# design.net
KiCad netlist of a schematic drawn in Altium Designer
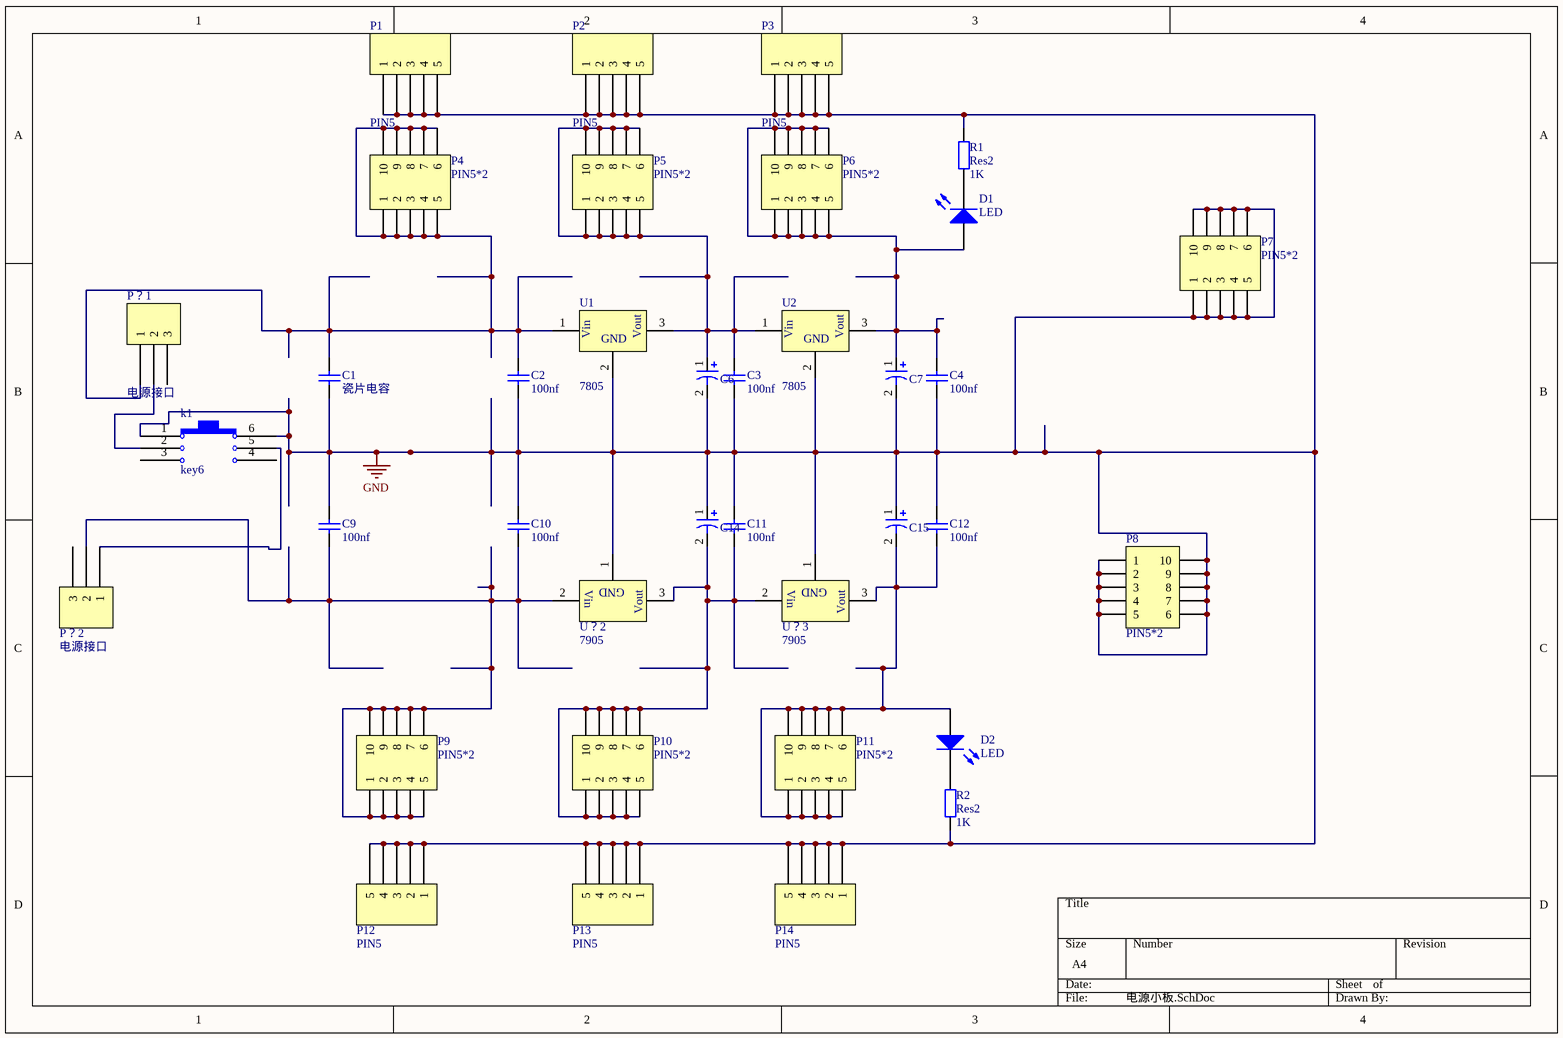
[diagram p0: 电源小板.SchDoc]

(export (version "E")
  (design (tool "Eeschema 10.0.6"))
  (components
    (comp (ref "C1") (value "瓷片电容") (footprint "PIN 2") (libsource (lib "胡瑶原理图库") (part "瓷片电容")))
    (comp (ref "C2") (value "100nf") (footprint "C瓷片电容") (libsource (lib "胡瑶原理图库") (part "C电容")))
    (comp (ref "C3") (value "100nf") (footprint "C瓷片电容") (libsource (lib "胡瑶原理图库") (part "C电容")))
    (comp (ref "C4") (value "100nf") (footprint "C瓷片电容") (libsource (lib "胡瑶原理图库") (part "C电容")))
    (comp (ref "C6") (value "C电解电容") (footprint "C (10,100,330UF)") (libsource (lib "胡瑶原理图库") (part "C电解电容")))
    (comp (ref "C7") (value "C电解电容") (footprint "C (10,100,330UF)") (libsource (lib "胡瑶原理图库") (part "C电解电容")))
    (comp (ref "C9") (value "100nf") (footprint "C瓷片电容") (libsource (lib "胡瑶原理图库") (part "C电容")))
    (comp (ref "C10") (value "100nf") (footprint "C瓷片电容") (libsource (lib "胡瑶原理图库") (part "C电容")))
    (comp (ref "C11") (value "100nf") (footprint "C瓷片电容") (libsource (lib "胡瑶原理图库") (part "C电容")))
    (comp (ref "C12") (value "100nf") (footprint "C瓷片电容") (libsource (lib "胡瑶原理图库") (part "C电容")))
    (comp (ref "C14")
      (value "C电解电容")
      (footprint "C (10,100,330UF)")
      (libsource (lib "胡瑶原理图库") (part "C电解电容"))
    )
    (comp (ref "C15")
      (value "C电解电容")
      (footprint "C (10,100,330UF)")
      (libsource (lib "胡瑶原理图库") (part "C电解电容"))
    )
    (comp (ref "D1") (value "LED") (footprint "LED") (libsource (lib "胡瑶原理图库") (part "LED")))
    (comp (ref "D2") (value "LED") (footprint "LED") (libsource (lib "胡瑶原理图库") (part "LED")))
    (comp (ref "k1") (value "key6") (footprint "key6") (libsource (lib "胡瑶原理图库") (part "key6")))
    (comp (ref "P1") (value "PIN5") (footprint "PIN5") (libsource (lib "") (part "PIN5_1")))
    (comp (ref "P2") (value "PIN5") (footprint "PIN5") (libsource (lib "") (part "PIN5_1")))
    (comp (ref "P3") (value "PIN5") (footprint "PIN5") (libsource (lib "") (part "PIN5_1")))
    (comp (ref "P4") (value "PIN5*2") (footprint "PIN5*2") (libsource (lib "胡瑶原理图库") (part "PIN5*2")))
    (comp (ref "P5") (value "PIN5*2") (footprint "PIN5*2") (libsource (lib "胡瑶原理图库") (part "PIN5*2")))
    (comp (ref "P6") (value "PIN5*2") (footprint "PIN5*2") (libsource (lib "胡瑶原理图库") (part "PIN5*2")))
    (comp (ref "P7") (value "PIN5*2") (footprint "PIN5*2") (libsource (lib "胡瑶原理图库") (part "PIN5*2")))
    (comp (ref "P8") (value "PIN5*2") (footprint "PIN5*2") (libsource (lib "") (part "PIN5*2_1")))
    (comp (ref "P9") (value "PIN5*2") (footprint "PIN5*2") (libsource (lib "胡瑶原理图库") (part "PIN5*2")))
    (comp (ref "P10") (value "PIN5*2") (footprint "PIN5*2") (libsource (lib "胡瑶原理图库") (part "PIN5*2")))
    (comp (ref "P11") (value "PIN5*2") (footprint "PIN5*2") (libsource (lib "胡瑶原理图库") (part "PIN5*2")))
    (comp (ref "P12") (value "PIN5") (footprint "PIN5") (libsource (lib "胡瑶原理图库") (part "PIN5")))
    (comp (ref "P13") (value "PIN5") (footprint "PIN5") (libsource (lib "胡瑶原理图库") (part "PIN5")))
    (comp (ref "P14") (value "PIN5") (footprint "PIN5") (libsource (lib "胡瑶原理图库") (part "PIN5")))
    (comp (ref "P？1") (value "电源接口") (footprint "电源接口") (libsource (lib "") (part "电源接口_1")))
    (comp (ref "P？2") (value "电源接口") (footprint "电源接口") (libsource (lib "胡瑶原理图库") (part "电源接口")))
    (comp (ref "R1")
      (value "Res2")
      (footprint "AXIAL-0.4")
      (description "Resistor")
      (fields (field (name "ALTIUM_VALUE") "1K") (field (name "PUBLISHER") "Altium Limited"))
      (libsource (lib "Miscellaneous Devices") (part "Res2"))
    )
    (comp (ref "R2")
      (value "Res2")
      (footprint "AXIAL-0.4")
      (description "Resistor")
      (fields (field (name "ALTIUM_VALUE") "1K") (field (name "PUBLISHER") "Altium Limited"))
      (libsource (lib "Miscellaneous Devices") (part "Res2"))
    )
    (comp (ref "U1") (value "7805") (footprint "7805") (libsource (lib "胡瑶原理图库") (part "7805")))
    (comp (ref "U2") (value "7805") (footprint "7805") (libsource (lib "胡瑶原理图库") (part "7805")))
    (comp (ref "U？2") (value "7905") (footprint "7805") (libsource (lib "胡瑶原理图库") (part "7905")))
    (comp (ref "U？3") (value "7905") (footprint "7805") (libsource (lib "胡瑶原理图库") (part "7905")))
  )
  (nets
    (net (code "1") (name "GND") (class "Default")
      (node (ref "C1") (pin "1") (pinfunction "1_1") (pintype "passive"))
      (node (ref "C10") (pin "2") (pinfunction "2_2") (pintype "passive"))
      (node (ref "C11") (pin "2") (pinfunction "2_2") (pintype "passive"))
      (node (ref "C12") (pin "2") (pinfunction "2_2") (pintype "passive"))
      (node (ref "C14") (pin "1") (pinfunction "1_1") (pintype "passive"))
      (node (ref "C15") (pin "1") (pinfunction "1_1") (pintype "passive"))
      (node (ref "C2") (pin "1") (pinfunction "1_1") (pintype "passive"))
      (node (ref "C3") (pin "1") (pinfunction "1_1") (pintype "passive"))
      (node (ref "C4") (pin "1") (pinfunction "1_1") (pintype "passive"))
      (node (ref "C6") (pin "2") (pinfunction "2_2") (pintype "passive"))
      (node (ref "C7") (pin "2") (pinfunction "2_2") (pintype "passive"))
      (node (ref "C9") (pin "2") (pinfunction "2_2") (pintype "passive"))
      (node (ref "P1") (pin "1") (pinfunction "1_1") (pintype "passive"))
      (node (ref "P1") (pin "2") (pinfunction "2_2") (pintype "passive"))
      (node (ref "P1") (pin "3") (pinfunction "3_3") (pintype "passive"))
      (node (ref "P1") (pin "4") (pinfunction "4_4") (pintype "passive"))
      (node (ref "P1") (pin "5") (pinfunction "5_5") (pintype "passive"))
      (node (ref "P12") (pin "1") (pinfunction "1_1") (pintype "passive"))
      (node (ref "P12") (pin "2") (pinfunction "2_2") (pintype "passive"))
      (node (ref "P12") (pin "3") (pinfunction "3_3") (pintype "passive"))
      (node (ref "P12") (pin "4") (pinfunction "4_4") (pintype "passive"))
      (node (ref "P12") (pin "5") (pinfunction "5_5") (pintype "passive"))
      (node (ref "P13") (pin "1") (pinfunction "1_1") (pintype "passive"))
      (node (ref "P13") (pin "2") (pinfunction "2_2") (pintype "passive"))
      (node (ref "P13") (pin "3") (pinfunction "3_3") (pintype "passive"))
      (node (ref "P13") (pin "4") (pinfunction "4_4") (pintype "passive"))
      (node (ref "P13") (pin "5") (pinfunction "5_5") (pintype "passive"))
      (node (ref "P14") (pin "1") (pinfunction "1_1") (pintype "passive"))
      (node (ref "P14") (pin "2") (pinfunction "2_2") (pintype "passive"))
      (node (ref "P14") (pin "3") (pinfunction "3_3") (pintype "passive"))
      (node (ref "P14") (pin "4") (pinfunction "4_4") (pintype "passive"))
      (node (ref "P14") (pin "5") (pinfunction "5_5") (pintype "passive"))
      (node (ref "P2") (pin "1") (pinfunction "1_1") (pintype "passive"))
      (node (ref "P2") (pin "2") (pinfunction "2_2") (pintype "passive"))
      (node (ref "P2") (pin "3") (pinfunction "3_3") (pintype "passive"))
      (node (ref "P2") (pin "4") (pinfunction "4_4") (pintype "passive"))
      (node (ref "P2") (pin "5") (pinfunction "5_5") (pintype "passive"))
      (node (ref "P3") (pin "1") (pinfunction "1_1") (pintype "passive"))
      (node (ref "P3") (pin "2") (pinfunction "2_2") (pintype "passive"))
      (node (ref "P3") (pin "3") (pinfunction "3_3") (pintype "passive"))
      (node (ref "P3") (pin "4") (pinfunction "4_4") (pintype "passive"))
      (node (ref "P3") (pin "5") (pinfunction "5_5") (pintype "passive"))
      (node (ref "P7") (pin "1") (pinfunction "1_1") (pintype "passive"))
      (node (ref "P7") (pin "10") (pinfunction "10_10") (pintype "passive"))
      (node (ref "P7") (pin "2") (pinfunction "2_2") (pintype "passive"))
      (node (ref "P7") (pin "3") (pinfunction "3_3") (pintype "passive"))
      (node (ref "P7") (pin "4") (pinfunction "4_4") (pintype "passive"))
      (node (ref "P7") (pin "5") (pinfunction "5_5") (pintype "passive"))
      (node (ref "P7") (pin "6") (pinfunction "6_6") (pintype "passive"))
      (node (ref "P7") (pin "7") (pinfunction "7_7") (pintype "passive"))
      (node (ref "P7") (pin "8") (pinfunction "8_8") (pintype "passive"))
      (node (ref "P7") (pin "9") (pinfunction "9_9") (pintype "passive"))
      (node (ref "P8") (pin "1") (pinfunction "1_1") (pintype "passive"))
      (node (ref "P8") (pin "10") (pinfunction "10_10") (pintype "passive"))
      (node (ref "P8") (pin "2") (pinfunction "2_2") (pintype "passive"))
      (node (ref "P8") (pin "3") (pinfunction "3_3") (pintype "passive"))
      (node (ref "P8") (pin "4") (pinfunction "4_4") (pintype "passive"))
      (node (ref "P8") (pin "5") (pinfunction "5_5") (pintype "passive"))
      (node (ref "P8") (pin "6") (pinfunction "6_6") (pintype "passive"))
      (node (ref "P8") (pin "7") (pinfunction "7_7") (pintype "passive"))
      (node (ref "P8") (pin "8") (pinfunction "8_8") (pintype "passive"))
      (node (ref "P8") (pin "9") (pinfunction "9_9") (pintype "passive"))
      (node (ref "R1") (pin "2") (pinfunction "2_2") (pintype "passive"))
      (node (ref "R2") (pin "1") (pinfunction "1_1") (pintype "passive"))
      (node (ref "U1") (pin "2") (pinfunction "gnd_2") (pintype "passive"))
      (node (ref "U2") (pin "2") (pinfunction "gnd_2") (pintype "passive"))
      (node (ref "U？2") (pin "1") (pinfunction "gnd_1") (pintype "passive"))
      (node (ref "U？3") (pin "1") (pinfunction "gnd_1") (pintype "passive"))
      (node (ref "k1") (pin "1") (pinfunction "1_1") (pintype "passive"))
      (node (ref "k1") (pin "6") (pinfunction "6_6") (pintype "passive"))
    )
    (net (code "2") (name "Net-(D1-A)") (class "Default")
      (node (ref "C4") (pin "2") (pinfunction "2_2") (pintype "passive"))
      (node (ref "C7") (pin "1") (pinfunction "1_1") (pintype "passive"))
      (node (ref "D1") (pin "1") (pinfunction "A_1") (pintype "passive"))
      (node (ref "P6") (pin "1") (pinfunction "1_1") (pintype "passive"))
      (node (ref "P6") (pin "10") (pinfunction "10_10") (pintype "passive"))
      (node (ref "P6") (pin "2") (pinfunction "2_2") (pintype "passive"))
      (node (ref "P6") (pin "3") (pinfunction "3_3") (pintype "passive"))
      (node (ref "P6") (pin "4") (pinfunction "4_4") (pintype "passive"))
      (node (ref "P6") (pin "5") (pinfunction "5_5") (pintype "passive"))
      (node (ref "P6") (pin "6") (pinfunction "6_6") (pintype "passive"))
      (node (ref "P6") (pin "7") (pinfunction "7_7") (pintype "passive"))
      (node (ref "P6") (pin "8") (pinfunction "8_8") (pintype "passive"))
      (node (ref "P6") (pin "9") (pinfunction "9_9") (pintype "passive"))
      (node (ref "U2") (pin "3") (pinfunction "Vout_3") (pintype "passive"))
    )
    (net (code "3") (name "Net-(D1-K)") (class "Default")
      (node (ref "D1") (pin "2") (pinfunction "K_2") (pintype "passive"))
      (node (ref "R1") (pin "1") (pinfunction "1_1") (pintype "passive"))
    )
    (net (code "4") (name "Net-(D2-A)") (class "Default")
      (node (ref "C12") (pin "1") (pinfunction "1_1") (pintype "passive"))
      (node (ref "C15") (pin "2") (pinfunction "2_2") (pintype "passive"))
      (node (ref "D2") (pin "1") (pinfunction "A_1") (pintype "passive"))
      (node (ref "P11") (pin "1") (pinfunction "1_1") (pintype "passive"))
      (node (ref "P11") (pin "10") (pinfunction "10_10") (pintype "passive"))
      (node (ref "P11") (pin "2") (pinfunction "2_2") (pintype "passive"))
      (node (ref "P11") (pin "3") (pinfunction "3_3") (pintype "passive"))
      (node (ref "P11") (pin "4") (pinfunction "4_4") (pintype "passive"))
      (node (ref "P11") (pin "5") (pinfunction "5_5") (pintype "passive"))
      (node (ref "P11") (pin "6") (pinfunction "6_6") (pintype "passive"))
      (node (ref "P11") (pin "7") (pinfunction "7_7") (pintype "passive"))
      (node (ref "P11") (pin "8") (pinfunction "8_8") (pintype "passive"))
      (node (ref "P11") (pin "9") (pinfunction "9_9") (pintype "passive"))
      (node (ref "U？3") (pin "3") (pinfunction "Vin_3") (pintype "passive"))
    )
    (net (code "5") (name "Net-(D2-K)") (class "Default")
      (node (ref "D2") (pin "2") (pinfunction "K_2") (pintype "passive"))
      (node (ref "R2") (pin "2") (pinfunction "2_2") (pintype "passive"))
    )
    (net (code "6") (name "Net-(P？1-Pad2)") (class "Default")
      (node (ref "P？1") (pin "2") (pinfunction "2_2") (pintype "passive"))
      (node (ref "k1") (pin "2") (pinfunction "2_2") (pintype "passive"))
    )
    (net (code "7") (name "Net-(P？2-Pad1)") (class "Default")
      (node (ref "P？2") (pin "1") (pinfunction "1_1") (pintype "passive"))
      (node (ref "k1") (pin "5") (pinfunction "5_5") (pintype "passive"))
    )
    (net (code "8") (name "Net-(U1-Vin)") (class "Default")
      (node (ref "C1") (pin "2") (pinfunction "2_2") (pintype "passive"))
      (node (ref "C2") (pin "2") (pinfunction "2_2") (pintype "passive"))
      (node (ref "P4") (pin "1") (pinfunction "1_1") (pintype "passive"))
      (node (ref "P4") (pin "10") (pinfunction "10_10") (pintype "passive"))
      (node (ref "P4") (pin "2") (pinfunction "2_2") (pintype "passive"))
      (node (ref "P4") (pin "3") (pinfunction "3_3") (pintype "passive"))
      (node (ref "P4") (pin "4") (pinfunction "4_4") (pintype "passive"))
      (node (ref "P4") (pin "5") (pinfunction "5_5") (pintype "passive"))
      (node (ref "P4") (pin "6") (pinfunction "6_6") (pintype "passive"))
      (node (ref "P4") (pin "7") (pinfunction "7_7") (pintype "passive"))
      (node (ref "P4") (pin "8") (pinfunction "8_8") (pintype "passive"))
      (node (ref "P4") (pin "9") (pinfunction "9_9") (pintype "passive"))
      (node (ref "P？1") (pin "1") (pinfunction "1_1") (pintype "passive"))
      (node (ref "U1") (pin "1") (pinfunction "Vin_1") (pintype "passive"))
    )
    (net (code "9") (name "Net-(U1-Vout)") (class "Default")
      (node (ref "C3") (pin "2") (pinfunction "2_2") (pintype "passive"))
      (node (ref "C6") (pin "1") (pinfunction "1_1") (pintype "passive"))
      (node (ref "P5") (pin "1") (pinfunction "1_1") (pintype "passive"))
      (node (ref "P5") (pin "10") (pinfunction "10_10") (pintype "passive"))
      (node (ref "P5") (pin "2") (pinfunction "2_2") (pintype "passive"))
      (node (ref "P5") (pin "3") (pinfunction "3_3") (pintype "passive"))
      (node (ref "P5") (pin "4") (pinfunction "4_4") (pintype "passive"))
      (node (ref "P5") (pin "5") (pinfunction "5_5") (pintype "passive"))
      (node (ref "P5") (pin "6") (pinfunction "6_6") (pintype "passive"))
      (node (ref "P5") (pin "7") (pinfunction "7_7") (pintype "passive"))
      (node (ref "P5") (pin "8") (pinfunction "8_8") (pintype "passive"))
      (node (ref "P5") (pin "9") (pinfunction "9_9") (pintype "passive"))
      (node (ref "U1") (pin "3") (pinfunction "Vout_3") (pintype "passive"))
      (node (ref "U2") (pin "1") (pinfunction "Vin_1") (pintype "passive"))
    )
    (net (code "10") (name "Net-(U？2-Vin)") (class "Default")
      (node (ref "C11") (pin "1") (pinfunction "1_1") (pintype "passive"))
      (node (ref "C14") (pin "2") (pinfunction "2_2") (pintype "passive"))
      (node (ref "P10") (pin "1") (pinfunction "1_1") (pintype "passive"))
      (node (ref "P10") (pin "10") (pinfunction "10_10") (pintype "passive"))
      (node (ref "P10") (pin "2") (pinfunction "2_2") (pintype "passive"))
      (node (ref "P10") (pin "3") (pinfunction "3_3") (pintype "passive"))
      (node (ref "P10") (pin "4") (pinfunction "4_4") (pintype "passive"))
      (node (ref "P10") (pin "5") (pinfunction "5_5") (pintype "passive"))
      (node (ref "P10") (pin "6") (pinfunction "6_6") (pintype "passive"))
      (node (ref "P10") (pin "7") (pinfunction "7_7") (pintype "passive"))
      (node (ref "P10") (pin "8") (pinfunction "8_8") (pintype "passive"))
      (node (ref "P10") (pin "9") (pinfunction "9_9") (pintype "passive"))
      (node (ref "U？2") (pin "3") (pinfunction "Vin_3") (pintype "passive"))
      (node (ref "U？3") (pin "2") (pinfunction "Vout_2") (pintype "passive"))
    )
    (net (code "11") (name "Net-(U？2-Vout)") (class "Default")
      (node (ref "C10") (pin "1") (pinfunction "1_1") (pintype "passive"))
      (node (ref "C9") (pin "1") (pinfunction "1_1") (pintype "passive"))
      (node (ref "P9") (pin "1") (pinfunction "1_1") (pintype "passive"))
      (node (ref "P9") (pin "10") (pinfunction "10_10") (pintype "passive"))
      (node (ref "P9") (pin "2") (pinfunction "2_2") (pintype "passive"))
      (node (ref "P9") (pin "3") (pinfunction "3_3") (pintype "passive"))
      (node (ref "P9") (pin "4") (pinfunction "4_4") (pintype "passive"))
      (node (ref "P9") (pin "5") (pinfunction "5_5") (pintype "passive"))
      (node (ref "P9") (pin "6") (pinfunction "6_6") (pintype "passive"))
      (node (ref "P9") (pin "7") (pinfunction "7_7") (pintype "passive"))
      (node (ref "P9") (pin "8") (pinfunction "8_8") (pintype "passive"))
      (node (ref "P9") (pin "9") (pinfunction "9_9") (pintype "passive"))
      (node (ref "P？2") (pin "2") (pinfunction "2_2") (pintype "passive"))
      (node (ref "U？2") (pin "2") (pinfunction "Vout_2") (pintype "passive"))
    )
    (net (code "12") (name "unconnected-(P？1-Pad3)") (class "Default")
      (node (ref "P？1") (pin "3") (pinfunction "3_3") (pintype "passive"))
    )
    (net (code "13") (name "unconnected-(P？2-Pad3)") (class "Default")
      (node (ref "P？2") (pin "3") (pinfunction "3_3") (pintype "passive"))
    )
    (net (code "14") (name "unconnected-(k1-Pad3)") (class "Default")
      (node (ref "k1") (pin "3") (pinfunction "3_3") (pintype "passive"))
    )
    (net (code "15") (name "unconnected-(k1-Pad4)") (class "Default")
      (node (ref "k1") (pin "4") (pinfunction "4_4") (pintype "passive"))
    )
  )
)
